# SAM3X-MCU.net
KiCad netlist of a schematic drawn in Altium Designer
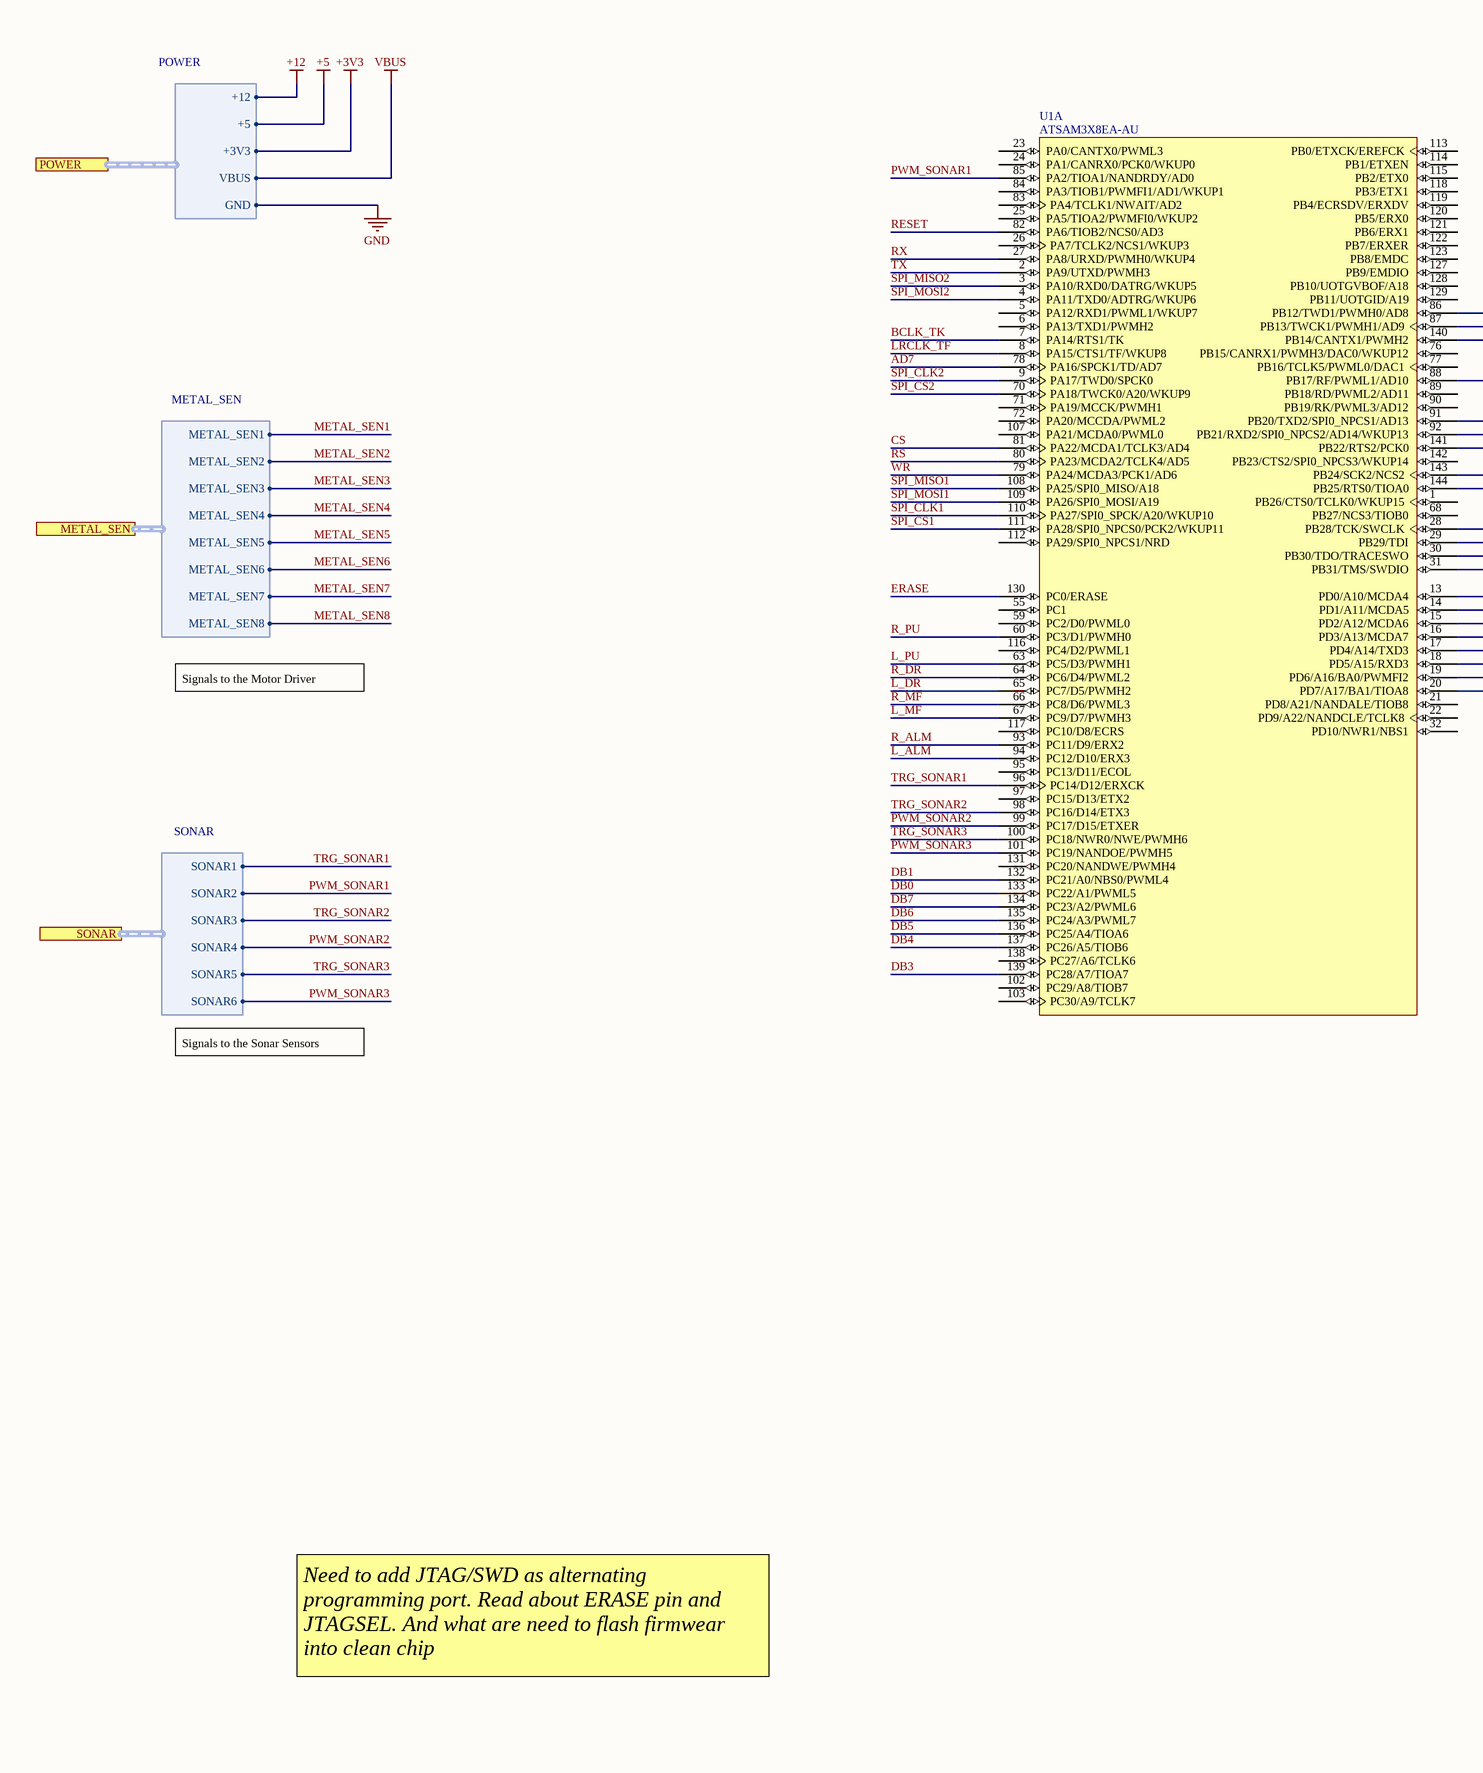
[diagram p0: SAM3X-MCU.SchDoc, left]
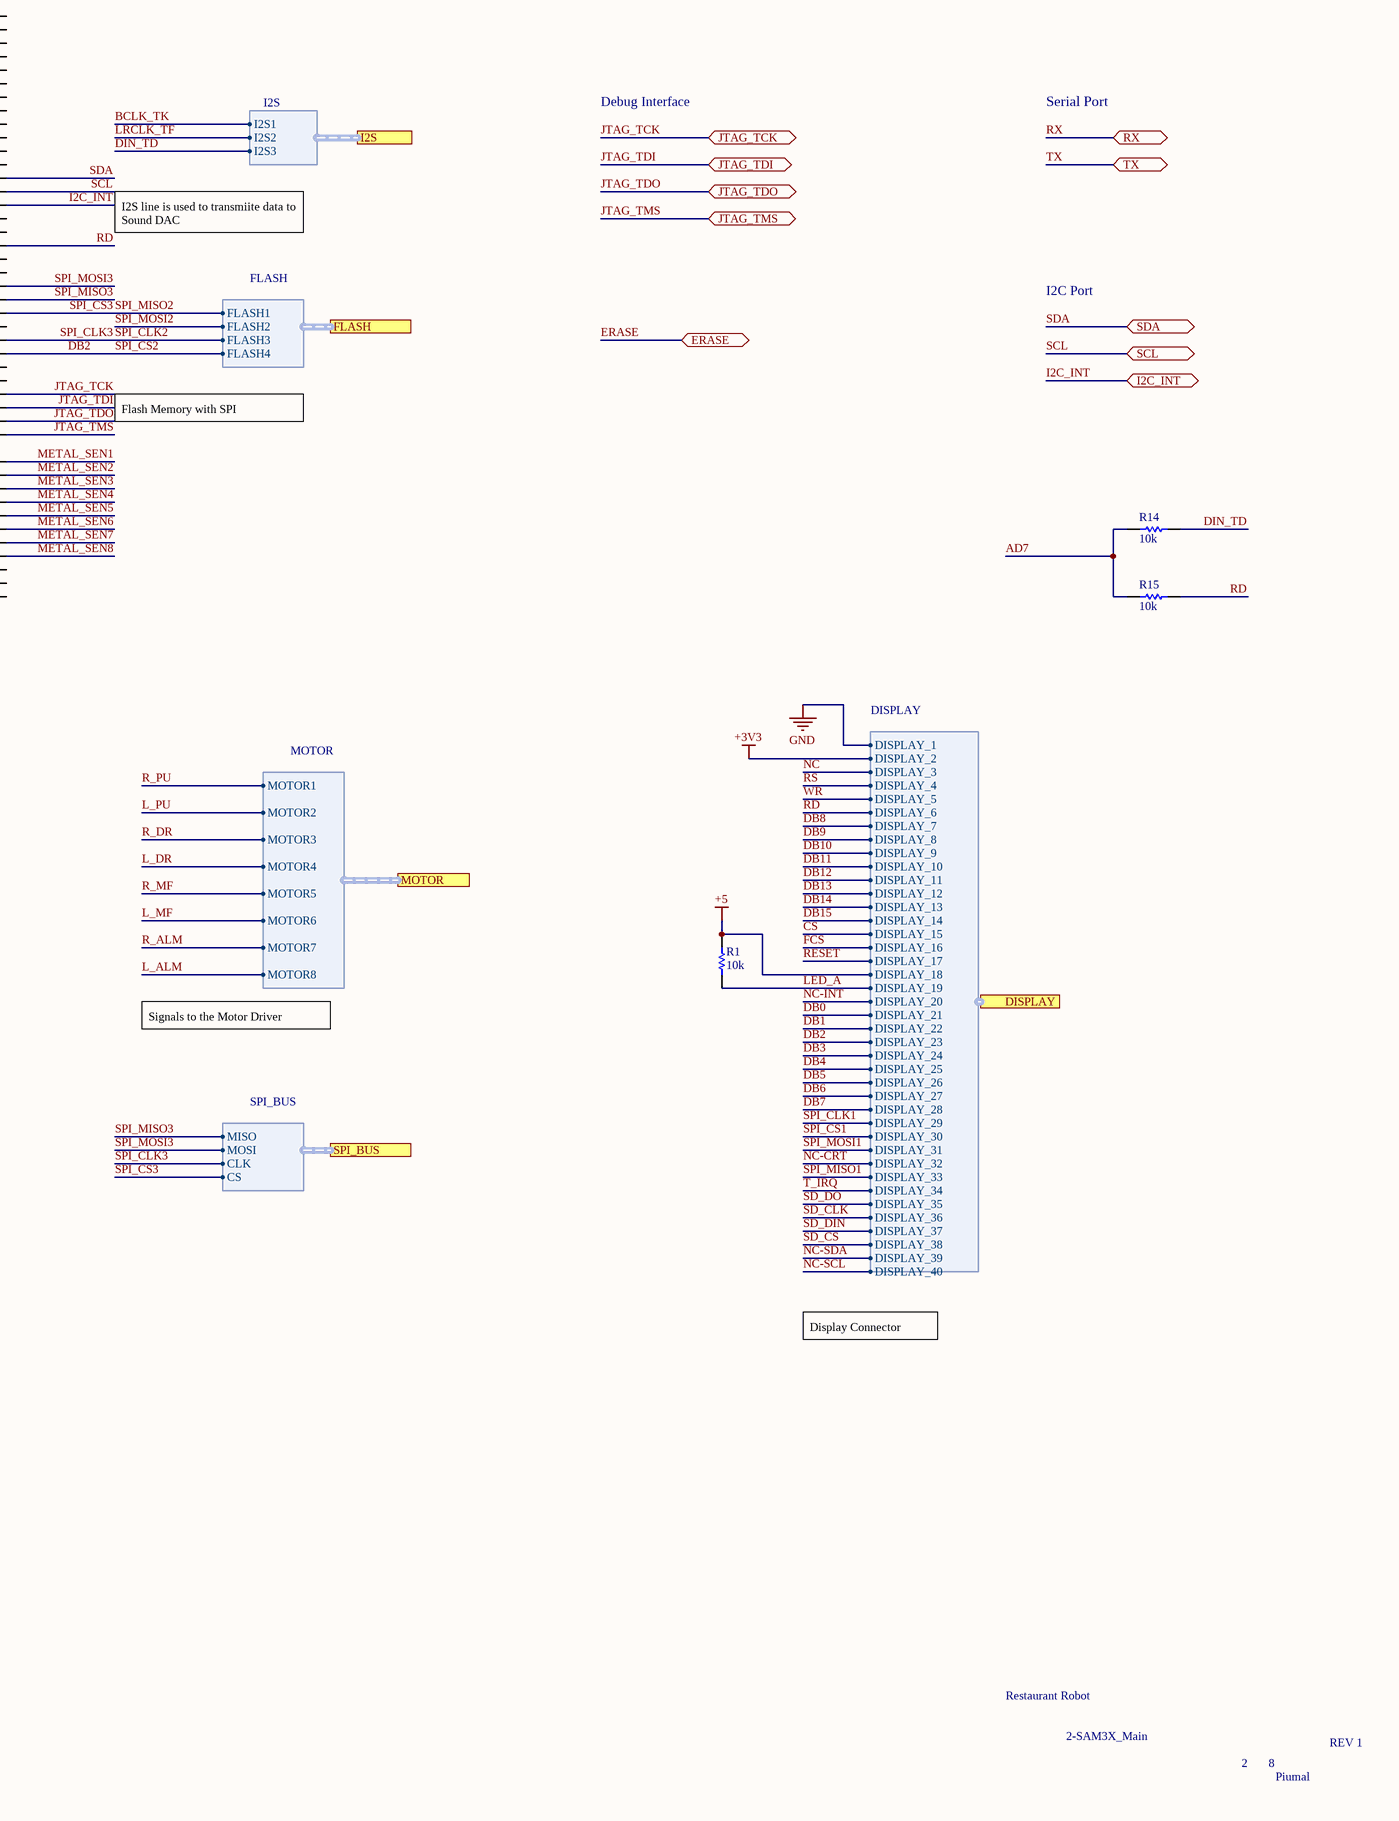
[diagram p1: SAM3X-MCU.SchDoc, right]

(export (version "E")
  (design (tool "Eeschema 10.0.6"))
  (components
    (comp (ref "R1")
      (value "RC0805JR-0710KL")
      (footprint "RESC2013X60X35ML10T20")
      (description "Chip Resistor, 10 KOhm, +/- 5%, 0.125 W, -55 to 155 degC, 0805 (2012 Metric), RoHS, Tape and Reel")
      (fields (field (name "MANUFACTURER") "Yageo") (field (name "RESISTANCE") "10k"))
      (libsource (lib "Altium Content Vault") (part "RES-2"))
    )
    (comp (ref "R14")
      (value "RC0805JR-0710KL")
      (footprint "RESC2013X60X35ML10T20")
      (description "Chip Resistor, 10 KOhm, +/- 5%, 0.125 W, -55 to 155 degC, 0805 (2012 Metric), RoHS, Tape and Reel")
      (fields (field (name "MANUFACTURER") "Yageo") (field (name "RESISTANCE") "10k"))
      (libsource (lib "Altium Content Vault") (part "RES-2"))
    )
    (comp (ref "R15")
      (value "RC0805JR-0710KL")
      (footprint "RESC2013X60X35ML10T20")
      (description "Chip Resistor, 10 KOhm, +/- 5%, 0.125 W, -55 to 155 degC, 0805 (2012 Metric), RoHS, Tape and Reel")
      (fields (field (name "MANUFACTURER") "Yageo") (field (name "RESISTANCE") "10k"))
      (libsource (lib "Altium Content Vault") (part "RES-2"))
    )
    (comp (ref "U1")
      (value "ATSAM3X8EA-AU")
      (footprint "LQFP144_M")
      (fields (field (name "MANUFACTURER") "Atmel"))
      (libsource (lib "Altium Content Vault") (part "ATML-ATSAM3X-LQFP-144"))
    )
  )
  (nets
    (net (code "10") (name "+5") (class "Default")
      (node (ref "R1") (pin "2") (pinfunction "2_2") (pintype "passive"))
    )
    (net (code "12") (name "/AD7") (class "Default")
      (node (ref "R14") (pin "2") (pinfunction "2_2") (pintype "passive"))
      (node (ref "R15") (pin "2") (pinfunction "2_2") (pintype "passive"))
      (node (ref "U1") (pin "78") (pinfunction "PA16/SPCK1/TD/AD7_78") (pintype "bidirectional"))
    )
    (net (code "13") (name "/BCLK_TK") (class "Default")
      (node (ref "U1") (pin "7") (pinfunction "PA14/RTS1/TK_7") (pintype "bidirectional"))
    )
    (net (code "14") (name "/CS") (class "Default")
      (node (ref "U1") (pin "81") (pinfunction "PA22/MCDA1/TCLK3/AD4_81") (pintype "bidirectional"))
    )
    (net (code "15") (name "/DB0") (class "Default")
      (node (ref "U1") (pin "133") (pinfunction "PC22/A1/PWML5_133") (pintype "bidirectional"))
    )
    (net (code "16") (name "/DB1") (class "Default")
      (node (ref "U1") (pin "132") (pinfunction "PC21/A0/NBS0/PWML4_132") (pintype "bidirectional"))
    )
    (net (code "17") (name "/DB2") (class "Default")
      (node (ref "U1") (pin "144") (pinfunction "PB25/RTS0/TIOA0_144") (pintype "bidirectional"))
      (node (ref "U1") (pin "70") (pinfunction "PA18/TWCK0/A20/WKUP9_70") (pintype "bidirectional"))
    )
    (net (code "18") (name "/DB3") (class "Default")
      (node (ref "U1") (pin "139") (pinfunction "PC28/A7/TIOA7_139") (pintype "bidirectional"))
    )
    (net (code "19") (name "/DB4") (class "Default")
      (node (ref "U1") (pin "137") (pinfunction "PC26/A5/TIOB6_137") (pintype "bidirectional"))
    )
    (net (code "20") (name "/DB5") (class "Default")
      (node (ref "U1") (pin "136") (pinfunction "PC25/A4/TIOA6_136") (pintype "bidirectional"))
    )
    (net (code "21") (name "/DB6") (class "Default")
      (node (ref "U1") (pin "135") (pinfunction "PC24/A3/PWML7_135") (pintype "bidirectional"))
    )
    (net (code "22") (name "/DB7") (class "Default")
      (node (ref "U1") (pin "134") (pinfunction "PC23/A2/PWML6_134") (pintype "bidirectional"))
    )
    (net (code "31") (name "/DIN_TD") (class "Default")
      (node (ref "R14") (pin "1") (pinfunction "1_1") (pintype "passive"))
    )
    (net (code "32") (name "/ERASE") (class "Default")
      (node (ref "U1") (pin "130") (pinfunction "PC0/ERASE_130") (pintype "bidirectional"))
    )
    (net (code "34") (name "/I2C_INT") (class "Default")
      (node (ref "U1") (pin "140") (pinfunction "PB14/CANTX1/PWMH2_140") (pintype "bidirectional"))
    )
    (net (code "35") (name "/JTAG_TCK") (class "Default")
      (node (ref "U1") (pin "28") (pinfunction "PB28/TCK/SWCLK_28") (pintype "bidirectional"))
    )
    (net (code "36") (name "/JTAG_TDI") (class "Default")
      (node (ref "U1") (pin "29") (pinfunction "PB29/TDI_29") (pintype "bidirectional"))
    )
    (net (code "37") (name "/JTAG_TDO") (class "Default")
      (node (ref "U1") (pin "30") (pinfunction "PB30/TDO/TRACESWO_30") (pintype "bidirectional"))
    )
    (net (code "38") (name "/JTAG_TMS") (class "Default")
      (node (ref "U1") (pin "31") (pinfunction "PB31/TMS/SWDIO_31") (pintype "bidirectional"))
    )
    (net (code "39") (name "/LED_A") (class "Default")
      (node (ref "R1") (pin "1") (pinfunction "1_1") (pintype "passive"))
    )
    (net (code "40") (name "/LRCLK_TF") (class "Default")
      (node (ref "U1") (pin "8") (pinfunction "PA15/CTS1/TF/WKUP8_8") (pintype "bidirectional"))
    )
    (net (code "41") (name "/L_ALM") (class "Default")
      (node (ref "U1") (pin "94") (pinfunction "PC12/D10/ERX3_94") (pintype "bidirectional"))
    )
    (net (code "42") (name "/L_DR") (class "Default")
      (node (ref "U1") (pin "65") (pinfunction "PC7/D5/PWMH2_65") (pintype "bidirectional"))
    )
    (net (code "43") (name "/L_MF") (class "Default")
      (node (ref "U1") (pin "67") (pinfunction "PC9/D7/PWMH3_67") (pintype "bidirectional"))
    )
    (net (code "44") (name "/L_PU") (class "Default")
      (node (ref "U1") (pin "63") (pinfunction "PC5/D3/PWMH1_63") (pintype "bidirectional"))
    )
    (net (code "45") (name "/METAL_SEN1") (class "Default")
      (node (ref "U1") (pin "13") (pinfunction "PD0/A10/MCDA4_13") (pintype "bidirectional"))
    )
    (net (code "46") (name "/METAL_SEN2") (class "Default")
      (node (ref "U1") (pin "14") (pinfunction "PD1/A11/MCDA5_14") (pintype "bidirectional"))
    )
    (net (code "47") (name "/METAL_SEN3") (class "Default")
      (node (ref "U1") (pin "15") (pinfunction "PD2/A12/MCDA6_15") (pintype "bidirectional"))
    )
    (net (code "48") (name "/METAL_SEN4") (class "Default")
      (node (ref "U1") (pin "16") (pinfunction "PD3/A13/MCDA7_16") (pintype "bidirectional"))
    )
    (net (code "49") (name "/METAL_SEN5") (class "Default")
      (node (ref "U1") (pin "17") (pinfunction "PD4/A14/TXD3_17") (pintype "bidirectional"))
    )
    (net (code "50") (name "/METAL_SEN6") (class "Default")
      (node (ref "U1") (pin "18") (pinfunction "PD5/A15/RXD3_18") (pintype "bidirectional"))
    )
    (net (code "51") (name "/METAL_SEN7") (class "Default")
      (node (ref "U1") (pin "19") (pinfunction "PD6/A16/BA0/PWMFI2_19") (pintype "bidirectional"))
    )
    (net (code "52") (name "/METAL_SEN8") (class "Default")
      (node (ref "U1") (pin "20") (pinfunction "PD7/A17/BA1/TIOA8_20") (pintype "bidirectional"))
    )
    (net (code "58") (name "/PWM_SONAR1") (class "Default")
      (node (ref "U1") (pin "85") (pinfunction "PA2/TIOA1/NANDRDY/AD0_85") (pintype "bidirectional"))
    )
    (net (code "59") (name "/PWM_SONAR2") (class "Default")
      (node (ref "U1") (pin "99") (pinfunction "PC17/D15/ETXER_99") (pintype "bidirectional"))
    )
    (net (code "60") (name "/PWM_SONAR3") (class "Default")
      (node (ref "U1") (pin "101") (pinfunction "PC19/NANDOE/PWMH5_101") (pintype "bidirectional"))
    )
    (net (code "61") (name "/RD") (class "Default")
      (node (ref "R15") (pin "1") (pinfunction "1_1") (pintype "passive"))
      (node (ref "U1") (pin "88") (pinfunction "PB17/RF/PWML1/AD10_88") (pintype "bidirectional"))
    )
    (net (code "62") (name "/RESET") (class "Default")
      (node (ref "U1") (pin "82") (pinfunction "PA6/TIOB2/NCS0/AD3_82") (pintype "bidirectional"))
    )
    (net (code "63") (name "/RS") (class "Default")
      (node (ref "U1") (pin "80") (pinfunction "PA23/MCDA2/TCLK4/AD5_80") (pintype "bidirectional"))
    )
    (net (code "64") (name "/RX") (class "Default")
      (node (ref "U1") (pin "27") (pinfunction "PA8/URXD/PWMH0/WKUP4_27") (pintype "bidirectional"))
    )
    (net (code "65") (name "/R_ALM") (class "Default")
      (node (ref "U1") (pin "93") (pinfunction "PC11/D9/ERX2_93") (pintype "bidirectional"))
    )
    (net (code "66") (name "/R_DR") (class "Default")
      (node (ref "U1") (pin "64") (pinfunction "PC6/D4/PWML2_64") (pintype "bidirectional"))
    )
    (net (code "67") (name "/R_MF") (class "Default")
      (node (ref "U1") (pin "66") (pinfunction "PC8/D6/PWML3_66") (pintype "bidirectional"))
    )
    (net (code "68") (name "/R_PU") (class "Default")
      (node (ref "U1") (pin "60") (pinfunction "PC3/D1/PWMH0_60") (pintype "bidirectional"))
    )
    (net (code "69") (name "/SCL") (class "Default")
      (node (ref "U1") (pin "87") (pinfunction "PB13/TWCK1/PWMH1/AD9_87") (pintype "bidirectional"))
    )
    (net (code "70") (name "/SDA") (class "Default")
      (node (ref "U1") (pin "86") (pinfunction "PB12/TWD1/PWMH0/AD8_86") (pintype "bidirectional"))
    )
    (net (code "75") (name "/SPI_CLK1") (class "Default")
      (node (ref "U1") (pin "110") (pinfunction "PA27/SPI0_SPCK/A20/WKUP10_110") (pintype "bidirectional"))
    )
    (net (code "76") (name "/SPI_CLK2") (class "Default")
      (node (ref "U1") (pin "143") (pinfunction "PB24/SCK2/NCS2_143") (pintype "bidirectional"))
      (node (ref "U1") (pin "9") (pinfunction "PA17/TWD0/SPCK0_9") (pintype "bidirectional"))
    )
    (net (code "77") (name "/SPI_CS1") (class "Default")
      (node (ref "U1") (pin "111") (pinfunction "PA28/SPI0_NPCS0/PCK2/WKUP11_111") (pintype "bidirectional"))
    )
    (net (code "78") (name "/SPI_CS3") (class "Default")
      (node (ref "U1") (pin "141") (pinfunction "PB22/RTS2/PCK0_141") (pintype "bidirectional"))
      (node (ref "U1") (pin "3") (pinfunction "PA10/RXD0/DATRG/WKUP5_3") (pintype "bidirectional"))
    )
    (net (code "79") (name "/SPI_MISO1") (class "Default")
      (node (ref "U1") (pin "108") (pinfunction "PA25/SPI0_MISO/A18_108") (pintype "bidirectional"))
    )
    (net (code "80") (name "/SPI_MISO3") (class "Default")
      (node (ref "U1") (pin "92") (pinfunction "PB21/RXD2/SPI0_NPCS2/AD14/WKUP13_92") (pintype "bidirectional"))
    )
    (net (code "81") (name "/SPI_MOSI1") (class "Default")
      (node (ref "U1") (pin "109") (pinfunction "PA26/SPI0_MOSI/A19_109") (pintype "bidirectional"))
    )
    (net (code "82") (name "/SPI_MOSI2") (class "Default")
      (node (ref "U1") (pin "4") (pinfunction "PA11/TXD0/ADTRG/WKUP6_4") (pintype "bidirectional"))
    )
    (net (code "83") (name "/SPI_MOSI3") (class "Default")
      (node (ref "U1") (pin "91") (pinfunction "PB20/TXD2/SPI0_NPCS1/AD13_91") (pintype "bidirectional"))
    )
    (net (code "84") (name "/TRG_SONAR1") (class "Default")
      (node (ref "U1") (pin "96") (pinfunction "PC14/D12/ERXCK_96") (pintype "bidirectional"))
    )
    (net (code "85") (name "/TRG_SONAR2") (class "Default")
      (node (ref "U1") (pin "98") (pinfunction "PC16/D14/ETX3_98") (pintype "bidirectional"))
    )
    (net (code "86") (name "/TRG_SONAR3") (class "Default")
      (node (ref "U1") (pin "100") (pinfunction "PC18/NWR0/NWE/PWMH6_100") (pintype "bidirectional"))
    )
    (net (code "87") (name "/TX") (class "Default")
      (node (ref "U1") (pin "2") (pinfunction "PA9/UTXD/PWMH3_2") (pintype "bidirectional"))
    )
    (net (code "89") (name "/WR") (class "Default")
      (node (ref "U1") (pin "79") (pinfunction "PA24/MCDA3/PCK1/AD6_79") (pintype "bidirectional"))
    )
    (net (code "100") (name "unconnected-(U1A-PA0{slash}CANTX0{slash}PWML3-Pad23)") (class "Default")
      (node (ref "U1") (pin "23") (pinfunction "PA0/CANTX0/PWML3_23") (pintype "bidirectional"))
    )
    (net (code "101") (name "unconnected-(U1A-PA1{slash}CANRX0{slash}PCK0{slash}WKUP0-Pad24)") (class "Default")
      (node (ref "U1") (pin "24") (pinfunction "PA1/CANRX0/PCK0/WKUP0_24") (pintype "bidirectional"))
    )
    (net (code "102") (name "unconnected-(U1A-PA3{slash}TIOB1{slash}PWMFI1{slash}AD1{slash}WKUP1-Pad84)") (class "Default")
      (node (ref "U1") (pin "84") (pinfunction "PA3/TIOB1/PWMFI1/AD1/WKUP1_84") (pintype "bidirectional"))
    )
    (net (code "103") (name "unconnected-(U1A-PA4{slash}TCLK1{slash}NWAIT{slash}AD2-Pad83)") (class "Default")
      (node (ref "U1") (pin "83") (pinfunction "PA4/TCLK1/NWAIT/AD2_83") (pintype "bidirectional"))
    )
    (net (code "104") (name "unconnected-(U1A-PA5{slash}TIOA2{slash}PWMFI0{slash}WKUP2-Pad25)") (class "Default")
      (node (ref "U1") (pin "25") (pinfunction "PA5/TIOA2/PWMFI0/WKUP2_25") (pintype "bidirectional"))
    )
    (net (code "105") (name "unconnected-(U1A-PA7{slash}TCLK2{slash}NCS1{slash}WKUP3-Pad26)") (class "Default")
      (node (ref "U1") (pin "26") (pinfunction "PA7/TCLK2/NCS1/WKUP3_26") (pintype "bidirectional"))
    )
    (net (code "106") (name "unconnected-(U1A-PA12{slash}RXD1{slash}PWML1{slash}WKUP7-Pad5)") (class "Default")
      (node (ref "U1") (pin "5") (pinfunction "PA12/RXD1/PWML1/WKUP7_5") (pintype "bidirectional"))
    )
    (net (code "107") (name "unconnected-(U1A-PA13{slash}TXD1{slash}PWMH2-Pad6)") (class "Default")
      (node (ref "U1") (pin "6") (pinfunction "PA13/TXD1/PWMH2_6") (pintype "bidirectional"))
    )
    (net (code "108") (name "unconnected-(U1A-PA19{slash}MCCK{slash}PWMH1-Pad71)") (class "Default")
      (node (ref "U1") (pin "71") (pinfunction "PA19/MCCK/PWMH1_71") (pintype "bidirectional"))
    )
    (net (code "109") (name "unconnected-(U1A-PA20{slash}MCCDA{slash}PWML2-Pad72)") (class "Default")
      (node (ref "U1") (pin "72") (pinfunction "PA20/MCCDA/PWML2_72") (pintype "bidirectional"))
    )
    (net (code "110") (name "unconnected-(U1A-PA21{slash}MCDA0{slash}PWML0-Pad107)") (class "Default")
      (node (ref "U1") (pin "107") (pinfunction "PA21/MCDA0/PWML0_107") (pintype "bidirectional"))
    )
    (net (code "111") (name "unconnected-(U1A-PA29{slash}SPI0_NPCS1{slash}NRD-Pad112)") (class "Default")
      (node (ref "U1") (pin "112") (pinfunction "PA29/SPI0_NPCS1/NRD_112") (pintype "bidirectional"))
    )
    (net (code "112") (name "unconnected-(U1A-PB0{slash}ETXCK{slash}EREFCK-Pad113)") (class "Default")
      (node (ref "U1") (pin "113") (pinfunction "PB0/ETXCK/EREFCK_113") (pintype "bidirectional"))
    )
    (net (code "113") (name "unconnected-(U1A-PB1{slash}ETXEN-Pad114)") (class "Default")
      (node (ref "U1") (pin "114") (pinfunction "PB1/ETXEN_114") (pintype "bidirectional"))
    )
    (net (code "114") (name "unconnected-(U1A-PB2{slash}ETX0-Pad115)") (class "Default")
      (node (ref "U1") (pin "115") (pinfunction "PB2/ETX0_115") (pintype "bidirectional"))
    )
    (net (code "115") (name "unconnected-(U1A-PB3{slash}ETX1-Pad118)") (class "Default")
      (node (ref "U1") (pin "118") (pinfunction "PB3/ETX1_118") (pintype "bidirectional"))
    )
    (net (code "116") (name "unconnected-(U1A-PB4{slash}ECRSDV{slash}ERXDV-Pad119)") (class "Default")
      (node (ref "U1") (pin "119") (pinfunction "PB4/ECRSDV/ERXDV_119") (pintype "bidirectional"))
    )
    (net (code "117") (name "unconnected-(U1A-PB5{slash}ERX0-Pad120)") (class "Default")
      (node (ref "U1") (pin "120") (pinfunction "PB5/ERX0_120") (pintype "bidirectional"))
    )
    (net (code "118") (name "unconnected-(U1A-PB6{slash}ERX1-Pad121)") (class "Default")
      (node (ref "U1") (pin "121") (pinfunction "PB6/ERX1_121") (pintype "bidirectional"))
    )
    (net (code "119") (name "unconnected-(U1A-PB7{slash}ERXER-Pad122)") (class "Default")
      (node (ref "U1") (pin "122") (pinfunction "PB7/ERXER_122") (pintype "bidirectional"))
    )
    (net (code "120") (name "unconnected-(U1A-PB8{slash}EMDC-Pad123)") (class "Default")
      (node (ref "U1") (pin "123") (pinfunction "PB8/EMDC_123") (pintype "bidirectional"))
    )
    (net (code "121") (name "unconnected-(U1A-PB9{slash}EMDIO-Pad127)") (class "Default")
      (node (ref "U1") (pin "127") (pinfunction "PB9/EMDIO_127") (pintype "bidirectional"))
    )
    (net (code "122") (name "unconnected-(U1A-PB10{slash}UOTGVBOF{slash}A18-Pad128)") (class "Default")
      (node (ref "U1") (pin "128") (pinfunction "PB10/UOTGVBOF/A18_128") (pintype "bidirectional"))
    )
    (net (code "123") (name "unconnected-(U1A-PB11{slash}UOTGID{slash}A19-Pad129)") (class "Default")
      (node (ref "U1") (pin "129") (pinfunction "PB11/UOTGID/A19_129") (pintype "bidirectional"))
    )
    (net (code "124") (name "unconnected-(U1A-PB15{slash}CANRX1{slash}PWMH3{slash}DAC0{slash}WKUP12-Pad76)") (class "Default")
      (node (ref "U1") (pin "76") (pinfunction "PB15/CANRX1/PWMH3/DAC0/WKUP12_76") (pintype "bidirectional"))
    )
    (net (code "125") (name "unconnected-(U1A-PB16{slash}TCLK5{slash}PWML0{slash}DAC1-Pad77)") (class "Default")
      (node (ref "U1") (pin "77") (pinfunction "PB16/TCLK5/PWML0/DAC1_77") (pintype "bidirectional"))
    )
    (net (code "126") (name "unconnected-(U1A-PB18{slash}RD{slash}PWML2{slash}AD11-Pad89)") (class "Default")
      (node (ref "U1") (pin "89") (pinfunction "PB18/RD/PWML2/AD11_89") (pintype "bidirectional"))
    )
    (net (code "127") (name "unconnected-(U1A-PB19{slash}RK{slash}PWML3{slash}AD12-Pad90)") (class "Default")
      (node (ref "U1") (pin "90") (pinfunction "PB19/RK/PWML3/AD12_90") (pintype "bidirectional"))
    )
    (net (code "128") (name "unconnected-(U1A-PB23{slash}CTS2{slash}SPI0_NPCS3{slash}WKUP14-Pad142)") (class "Default")
      (node (ref "U1") (pin "142") (pinfunction "PB23/CTS2/SPI0_NPCS3/WKUP14_142") (pintype "bidirectional"))
    )
    (net (code "129") (name "unconnected-(U1A-PB26{slash}CTS0{slash}TCLK0{slash}WKUP15-Pad1)") (class "Default")
      (node (ref "U1") (pin "1") (pinfunction "PB26/CTS0/TCLK0/WKUP15_1") (pintype "bidirectional"))
    )
    (net (code "130") (name "unconnected-(U1A-PB27{slash}NCS3{slash}TIOB0-Pad68)") (class "Default")
      (node (ref "U1") (pin "68") (pinfunction "PB27/NCS3/TIOB0_68") (pintype "bidirectional"))
    )
    (net (code "131") (name "unconnected-(U1A-PC1-Pad55)") (class "Default")
      (node (ref "U1") (pin "55") (pinfunction "PC1_55") (pintype "bidirectional"))
    )
    (net (code "132") (name "unconnected-(U1A-PC2{slash}D0{slash}PWML0-Pad59)") (class "Default")
      (node (ref "U1") (pin "59") (pinfunction "PC2/D0/PWML0_59") (pintype "bidirectional"))
    )
    (net (code "133") (name "unconnected-(U1A-PC4{slash}D2{slash}PWML1-Pad116)") (class "Default")
      (node (ref "U1") (pin "116") (pinfunction "PC4/D2/PWML1_116") (pintype "bidirectional"))
    )
    (net (code "134") (name "unconnected-(U1A-PC10{slash}D8{slash}ECRS-Pad117)") (class "Default")
      (node (ref "U1") (pin "117") (pinfunction "PC10/D8/ECRS_117") (pintype "bidirectional"))
    )
    (net (code "135") (name "unconnected-(U1A-PC13{slash}D11{slash}ECOL-Pad95)") (class "Default")
      (node (ref "U1") (pin "95") (pinfunction "PC13/D11/ECOL_95") (pintype "bidirectional"))
    )
    (net (code "136") (name "unconnected-(U1A-PC15{slash}D13{slash}ETX2-Pad97)") (class "Default")
      (node (ref "U1") (pin "97") (pinfunction "PC15/D13/ETX2_97") (pintype "bidirectional"))
    )
    (net (code "137") (name "unconnected-(U1A-PC20{slash}NANDWE{slash}PWMH4-Pad131)") (class "Default")
      (node (ref "U1") (pin "131") (pinfunction "PC20/NANDWE/PWMH4_131") (pintype "bidirectional"))
    )
    (net (code "138") (name "unconnected-(U1A-PC27{slash}A6{slash}TCLK6-Pad138)") (class "Default")
      (node (ref "U1") (pin "138") (pinfunction "PC27/A6/TCLK6_138") (pintype "bidirectional"))
    )
    (net (code "139") (name "unconnected-(U1A-PC29{slash}A8{slash}TIOB7-Pad102)") (class "Default")
      (node (ref "U1") (pin "102") (pinfunction "PC29/A8/TIOB7_102") (pintype "bidirectional"))
    )
    (net (code "140") (name "unconnected-(U1A-PC30{slash}A9{slash}TCLK7-Pad103)") (class "Default")
      (node (ref "U1") (pin "103") (pinfunction "PC30/A9/TCLK7_103") (pintype "bidirectional"))
    )
    (net (code "141") (name "unconnected-(U1A-PD8{slash}A21{slash}NANDALE{slash}TIOB8-Pad21)") (class "Default")
      (node (ref "U1") (pin "21") (pinfunction "PD8/A21/NANDALE/TIOB8_21") (pintype "bidirectional"))
    )
    (net (code "142") (name "unconnected-(U1A-PD9{slash}A22{slash}NANDCLE{slash}TCLK8-Pad22)") (class "Default")
      (node (ref "U1") (pin "22") (pinfunction "PD9/A22/NANDCLE/TCLK8_22") (pintype "bidirectional"))
    )
    (net (code "143") (name "unconnected-(U1A-PD10{slash}NWR1{slash}NBS1-Pad32)") (class "Default")
      (node (ref "U1") (pin "32") (pinfunction "PD10/NWR1/NBS1_32") (pintype "bidirectional"))
    )
  )
)
